# RGBKeyFob.net
KiCad netlist of a schematic drawn in Altium Designer
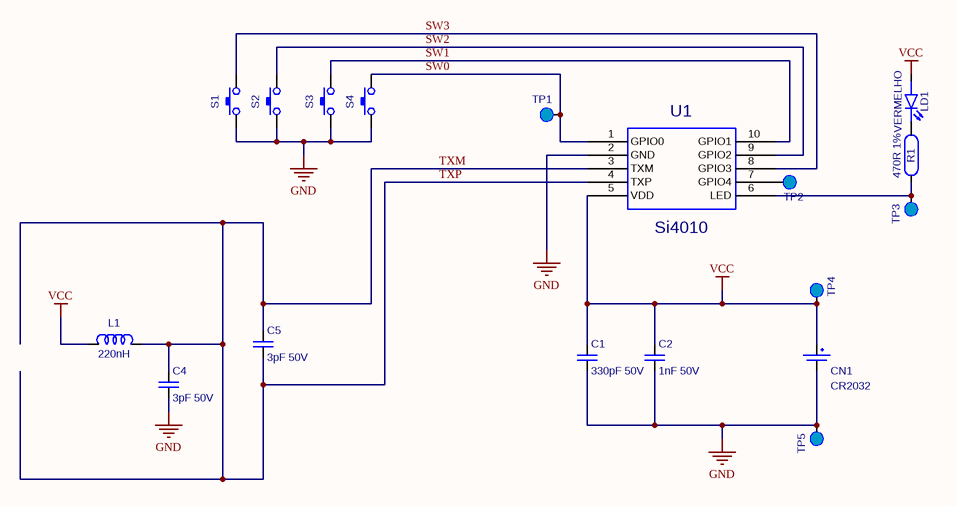
[diagram p0: RGBKeyFob.SchDoc]

(export (version "E")
  (design (tool "Eeschema 10.0.6"))
  (components
    (comp (ref "C1")
      (value "330pF 50V")
      (footprint "C0805")
      (fields (field (name "PART NUMBER") "08055A271JAT2A") (field (name "Comment") "270pF 50V"))
      (libsource (lib "GLOBUS_ALTIUM") (part "CC 270pF 50V 0805"))
    )
    (comp (ref "C2")
      (value "1nF 50V")
      (footprint "C0805")
      (libsource (lib "GLOBUS_ALTIUM") (part "CC 1nF 50V 0805"))
    )
    (comp (ref "C4")
      (value "3pF 50V")
      (footprint "C0805")
      (fields (field (name "PART NUMBER") "08055A3R0CAT2A"))
      (libsource (lib "GLOBUS_ALTIUM") (part "CC 3pF 50V 0805"))
    )
    (comp (ref "C5")
      (value "3pF 50V")
      (footprint "C0805")
      (fields (field (name "PART NUMBER") "08055A3R0CAT2A"))
      (libsource (lib "GLOBUS_ALTIUM") (part "CC 3pF 50V 0805"))
    )
    (comp (ref "CN1")
      (value "CR2032")
      (footprint "CR2032 LINX")
      (fields (field (name "PART NUMBER") "BAT-HLD-001") (field (name "Comment") "CR2032 LINX"))
      (libsource (lib "GLOBUS_ALTIUM") (part "SUPORTE BAT CR2032 LINX"))
    )
    (comp (ref "L1")
      (value "220nH")
      (footprint "I0805")
      (description "IND 220nH 0805 SMD")
      (fields (field (name "PART NUMBER") "CE201210-R22J"))
      (libsource (lib "GLOBUS_ALTIUM") (part "IND 220nH 0805 SMD"))
    )
    (comp (ref "LD1")
      (value "VERMELHO")
      (footprint "LED3MM-RED")
      (description "LED SMT 0805")
      (libsource (lib "GLOBUS_ALTIUM") (part "LED VM 3MM"))
    )
    (comp (ref "R1")
      (value "470R 1%")
      (footprint "R0805")
      (description "RES 470R 1% 0805")
      (fields (field (name "PART NUMBER") "{Part Number}"))
      (libsource (lib "GLOBUS_ALTIUM") (part "RES 470R 1% 0805"))
    )
    (comp (ref "S1")
      (value "TECLA SMD 4,3mm")
      (footprint "TECLA_TS-06M-ASM")
      (description "TECLA TACTIL 4,3MM SMD")
      (libsource (lib "GLOBUS_ALTIUM") (part "TEC TACTIL 4,3MM SMD"))
    )
    (comp (ref "S2")
      (value "TECLA SMD 4,3mm")
      (footprint "TECLA_TS-06M-ASM")
      (description "TECLA TACTIL 4,3MM SMD")
      (libsource (lib "GLOBUS_ALTIUM") (part "TEC TACTIL 4,3MM SMD"))
    )
    (comp (ref "S3")
      (value "TECLA SMD 4,3mm")
      (footprint "TECLA_TS-06M-ASM")
      (description "TECLA TACTIL 4,3MM SMD")
      (libsource (lib "GLOBUS_ALTIUM") (part "TEC TACTIL 4,3MM SMD"))
    )
    (comp (ref "S4")
      (value "TECLA SMD 4,3mm")
      (footprint "TECLA_TS-06M-ASM")
      (description "TECLA TACTIL 4,3MM SMD")
      (libsource (lib "GLOBUS_ALTIUM") (part "TEC TACTIL 4,3MM SMD"))
    )
    (comp (ref "TP1")
      (value "TestPoint SMD")
      (footprint "TestPointSMD")
      (fields (field (name "PART NUMBER") "????"))
      (libsource (lib "GLOBUS_ALTIUM") (part "TestPoint SMD"))
    )
    (comp (ref "TP2")
      (value "TestPoint SMD")
      (footprint "TestPointSMD")
      (fields (field (name "PART NUMBER") "????"))
      (libsource (lib "GLOBUS_ALTIUM") (part "TestPoint SMD"))
    )
    (comp (ref "TP3")
      (value "TestPoint SMD")
      (footprint "TestPointSMD")
      (fields (field (name "PART NUMBER") "????"))
      (libsource (lib "GLOBUS_ALTIUM") (part "TestPoint SMD"))
    )
    (comp (ref "TP4")
      (value "TestPoint SMD")
      (footprint "TestPointSMD")
      (fields (field (name "PART NUMBER") "????"))
      (libsource (lib "GLOBUS_ALTIUM") (part "TestPoint SMD"))
    )
    (comp (ref "TP5")
      (value "TestPoint SMD")
      (footprint "TestPointSMD")
      (fields (field (name "PART NUMBER") "????"))
      (libsource (lib "GLOBUS_ALTIUM") (part "TestPoint SMD"))
    )
    (comp (ref "U1")
      (value "Si4010")
      (footprint "MSOP-10")
      (description "CI Si4010-C2-GT MSOP-10")
      (fields (field (name "PART NUMBER") "Si4010-C2-GT"))
      (libsource (lib "GLOBUS_ALTIUM") (part "CI Si4010-C2-GT MSOP-10"))
    )
  )
  (nets
    (net (code "1") (name "/SW0") (class "Default")
      (node (ref "S4") (pin "1") (pinfunction "1_1") (pintype "passive"))
      (node (ref "TP1") (pin "1") (pinfunction "1_1") (pintype "passive"))
      (node (ref "U1") (pin "1") (pinfunction "GPIO0_1") (pintype "passive"))
    )
    (net (code "2") (name "/SW1") (class "Default")
      (node (ref "S3") (pin "1") (pinfunction "1_1") (pintype "passive"))
      (node (ref "U1") (pin "10") (pinfunction "GPIO1_10") (pintype "passive"))
    )
    (net (code "3") (name "/SW2") (class "Default")
      (node (ref "S2") (pin "1") (pinfunction "1_1") (pintype "passive"))
      (node (ref "U1") (pin "9") (pinfunction "GPIO2_9") (pintype "passive"))
    )
    (net (code "4") (name "/SW3") (class "Default")
      (node (ref "S1") (pin "1") (pinfunction "1_1") (pintype "passive"))
      (node (ref "U1") (pin "8") (pinfunction "GPIO3_8") (pintype "passive"))
    )
    (net (code "5") (name "/TXM") (class "Default")
      (node (ref "C4") (pin "1") (pinfunction "1_1") (pintype "passive"))
      (node (ref "C5") (pin "1") (pinfunction "1_1") (pintype "passive"))
      (node (ref "C5") (pin "2") (pinfunction "2_2") (pintype "passive"))
      (node (ref "L1") (pin "2") (pinfunction "2_2") (pintype "passive"))
      (node (ref "U1") (pin "3") (pinfunction "TXM_3") (pintype "passive"))
      (node (ref "U1") (pin "4") (pinfunction "TXP_4") (pintype "passive"))
    )
    (net (code "6") (name "GND") (class "Default")
      (node (ref "C1") (pin "2") (pinfunction "2_2") (pintype "passive"))
      (node (ref "C2") (pin "2") (pinfunction "2_2") (pintype "passive"))
      (node (ref "C4") (pin "2") (pinfunction "2_2") (pintype "passive"))
      (node (ref "CN1") (pin "2") (pinfunction "2_2") (pintype "passive"))
      (node (ref "S1") (pin "2") (pinfunction "2_2") (pintype "passive"))
      (node (ref "S2") (pin "2") (pinfunction "2_2") (pintype "passive"))
      (node (ref "S3") (pin "2") (pinfunction "2_2") (pintype "passive"))
      (node (ref "S4") (pin "2") (pinfunction "2_2") (pintype "passive"))
      (node (ref "TP5") (pin "1") (pinfunction "1_1") (pintype "passive"))
      (node (ref "U1") (pin "2") (pinfunction "GND_2") (pintype "passive"))
    )
    (net (code "7") (name "Net-(LD1-cathode)") (class "Default")
      (node (ref "LD1") (pin "2") (pinfunction "cathode_2") (pintype "passive"))
      (node (ref "R1") (pin "2") (pinfunction "2_2") (pintype "passive"))
    )
    (net (code "8") (name "Net-(U1-GPIO4)") (class "Default")
      (node (ref "TP2") (pin "1") (pinfunction "1_1") (pintype "passive"))
      (node (ref "U1") (pin "7") (pinfunction "GPIO4_7") (pintype "passive"))
    )
    (net (code "9") (name "Net-(U1-LED)") (class "Default")
      (node (ref "R1") (pin "1") (pinfunction "1_1") (pintype "passive"))
      (node (ref "TP3") (pin "1") (pinfunction "1_1") (pintype "passive"))
      (node (ref "U1") (pin "6") (pinfunction "LED_6") (pintype "passive"))
    )
    (net (code "10") (name "VCC") (class "Default")
      (node (ref "C1") (pin "1") (pinfunction "1_1") (pintype "passive"))
      (node (ref "C2") (pin "1") (pinfunction "1_1") (pintype "passive"))
      (node (ref "CN1") (pin "1") (pinfunction "1_1") (pintype "passive"))
      (node (ref "L1") (pin "1") (pinfunction "1_1") (pintype "passive"))
      (node (ref "LD1") (pin "1") (pinfunction "anode_1") (pintype "passive"))
      (node (ref "TP4") (pin "1") (pinfunction "1_1") (pintype "passive"))
      (node (ref "U1") (pin "5") (pinfunction "VDD_5") (pintype "passive"))
    )
  )
)
